# board.net
KiCad netlist of a schematic drawn in EAGLE
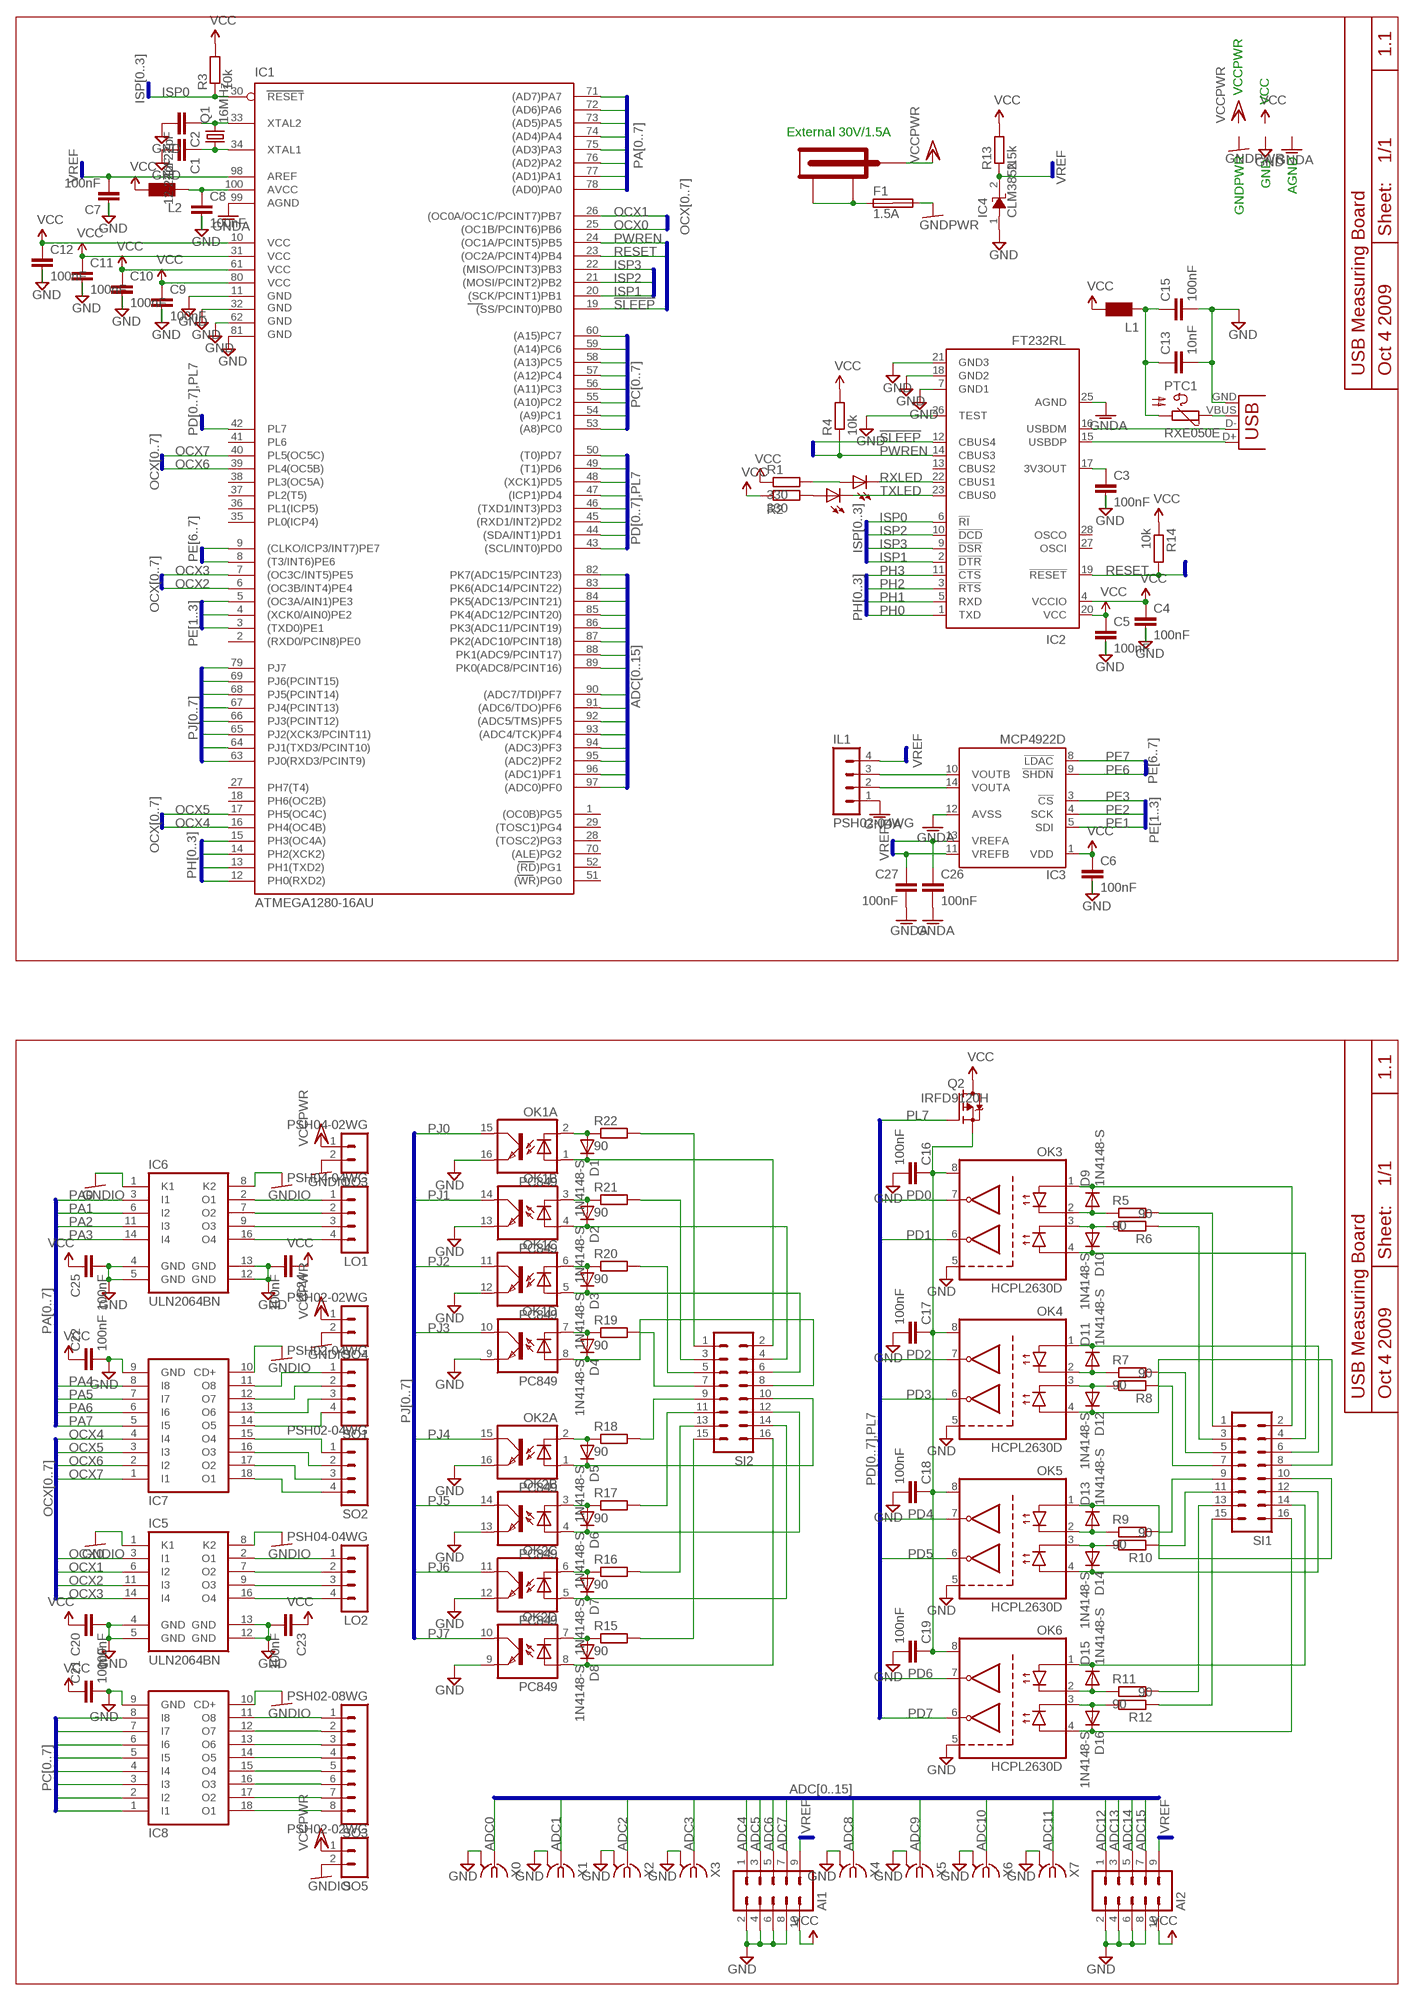
[diagram p0: schematic, sheet 1]

(export (version "E")
  (design (tool "Eeschema 10.0.6"))
  (components
    (comp (ref "AI1")
      (value "ML10")
      (footprint "eagle-import:ML10")
      (libsource (lib "eagle-import") (part "ML10"))
    )
    (comp (ref "AI2")
      (value "ML10")
      (footprint "eagle-import:ML10")
      (libsource (lib "eagle-import") (part "ML10"))
    )
    (comp (ref "C1")
      (value "12-22pF")
      (footprint "eagle-import:C0805K")
      (libsource (lib "eagle-import") (part "C-EUC0805K"))
    )
    (comp (ref "C2")
      (value "12-22pF")
      (footprint "eagle-import:C0805K")
      (libsource (lib "eagle-import") (part "C-EUC0805K"))
    )
    (comp (ref "C3")
      (value "100nF")
      (footprint "eagle-import:C0805K")
      (libsource (lib "eagle-import") (part "C-EUC0805K"))
    )
    (comp (ref "C4")
      (value "100nF")
      (footprint "eagle-import:C0805K")
      (libsource (lib "eagle-import") (part "C-EUC0805K"))
    )
    (comp (ref "C5")
      (value "100nF")
      (footprint "eagle-import:C0805K")
      (libsource (lib "eagle-import") (part "C-EUC0805K"))
    )
    (comp (ref "C6")
      (value "100nF")
      (footprint "eagle-import:C0805K")
      (libsource (lib "eagle-import") (part "C-EUC0805K"))
    )
    (comp (ref "C7")
      (value "100nF")
      (footprint "eagle-import:C0805K")
      (libsource (lib "eagle-import") (part "C-EUC0805K"))
    )
    (comp (ref "C8")
      (value "100nF")
      (footprint "eagle-import:C0805K")
      (libsource (lib "eagle-import") (part "C-EUC0805K"))
    )
    (comp (ref "C9")
      (value "100nF")
      (footprint "eagle-import:C0805K")
      (libsource (lib "eagle-import") (part "C-EUC0805K"))
    )
    (comp (ref "C10")
      (value "100nF")
      (footprint "eagle-import:C0805K")
      (libsource (lib "eagle-import") (part "C-EUC0805K"))
    )
    (comp (ref "C11")
      (value "100nF")
      (footprint "eagle-import:C0805K")
      (libsource (lib "eagle-import") (part "C-EUC0805K"))
    )
    (comp (ref "C12")
      (value "100nF")
      (footprint "eagle-import:C0805K")
      (libsource (lib "eagle-import") (part "C-EUC0805K"))
    )
    (comp (ref "C13")
      (value "10nF")
      (footprint "eagle-import:C0805K")
      (libsource (lib "eagle-import") (part "C-EUC0805K"))
    )
    (comp (ref "C15")
      (value "100nF")
      (footprint "eagle-import:C0805K")
      (libsource (lib "eagle-import") (part "C-EUC0805K"))
    )
    (comp (ref "C16")
      (value "100nF")
      (footprint "eagle-import:C0805K")
      (libsource (lib "eagle-import") (part "C-EUC0805K"))
    )
    (comp (ref "C17")
      (value "100nF")
      (footprint "eagle-import:C0805K")
      (libsource (lib "eagle-import") (part "C-EUC0805K"))
    )
    (comp (ref "C18")
      (value "100nF")
      (footprint "eagle-import:C0805K")
      (libsource (lib "eagle-import") (part "C-EUC0805K"))
    )
    (comp (ref "C19")
      (value "100nF")
      (footprint "eagle-import:C0805K")
      (libsource (lib "eagle-import") (part "C-EUC0805K"))
    )
    (comp (ref "C20")
      (value "100nF")
      (footprint "eagle-import:C0805K")
      (libsource (lib "eagle-import") (part "C-EUC0805K"))
    )
    (comp (ref "C21")
      (value "100nF")
      (footprint "eagle-import:C0805K")
      (libsource (lib "eagle-import") (part "C-EUC0805K"))
    )
    (comp (ref "C22")
      (value "100nF")
      (footprint "eagle-import:C0805K")
      (libsource (lib "eagle-import") (part "C-EUC0805K"))
    )
    (comp (ref "C23")
      (value "100nF")
      (footprint "eagle-import:C0805K")
      (libsource (lib "eagle-import") (part "C-EUC0805K"))
    )
    (comp (ref "C24")
      (value "100nF")
      (footprint "eagle-import:C0805K")
      (libsource (lib "eagle-import") (part "C-EUC0805K"))
    )
    (comp (ref "C25")
      (value "100nF")
      (footprint "eagle-import:C0805K")
      (libsource (lib "eagle-import") (part "C-EUC0805K"))
    )
    (comp (ref "C26")
      (value "100nF")
      (footprint "eagle-import:C0805K")
      (libsource (lib "eagle-import") (part "C-EUC0805K"))
    )
    (comp (ref "C27")
      (value "100nF")
      (footprint "eagle-import:C0805K")
      (libsource (lib "eagle-import") (part "C-EUC0805K"))
    )
    (comp (ref "CON1")
      (value "PWR-PCB")
      (footprint "eagle-import:PWR")
      (libsource (lib "eagle-import") (part "PWR-PCB"))
    )
    (comp (ref "D1")
      (value "1N4148-S")
      (footprint "eagle-import:D0805")
      (libsource (lib "eagle-import") (part "1N4148-S"))
    )
    (comp (ref "D2")
      (value "1N4148-S")
      (footprint "eagle-import:D0805")
      (libsource (lib "eagle-import") (part "1N4148-S"))
    )
    (comp (ref "D3")
      (value "1N4148-S")
      (footprint "eagle-import:D0805")
      (libsource (lib "eagle-import") (part "1N4148-S"))
    )
    (comp (ref "D4")
      (value "1N4148-S")
      (footprint "eagle-import:D0805")
      (libsource (lib "eagle-import") (part "1N4148-S"))
    )
    (comp (ref "D5")
      (value "1N4148-S")
      (footprint "eagle-import:D0805")
      (libsource (lib "eagle-import") (part "1N4148-S"))
    )
    (comp (ref "D6")
      (value "1N4148-S")
      (footprint "eagle-import:D0805")
      (libsource (lib "eagle-import") (part "1N4148-S"))
    )
    (comp (ref "D7")
      (value "1N4148-S")
      (footprint "eagle-import:D0805")
      (libsource (lib "eagle-import") (part "1N4148-S"))
    )
    (comp (ref "D8")
      (value "1N4148-S")
      (footprint "eagle-import:D0805")
      (libsource (lib "eagle-import") (part "1N4148-S"))
    )
    (comp (ref "D9")
      (value "1N4148-S")
      (footprint "eagle-import:D0805")
      (libsource (lib "eagle-import") (part "1N4148-S"))
    )
    (comp (ref "D10")
      (value "1N4148-S")
      (footprint "eagle-import:D0805")
      (libsource (lib "eagle-import") (part "1N4148-S"))
    )
    (comp (ref "D11")
      (value "1N4148-S")
      (footprint "eagle-import:D0805")
      (libsource (lib "eagle-import") (part "1N4148-S"))
    )
    (comp (ref "D12")
      (value "1N4148-S")
      (footprint "eagle-import:D0805")
      (libsource (lib "eagle-import") (part "1N4148-S"))
    )
    (comp (ref "D13")
      (value "1N4148-S")
      (footprint "eagle-import:D0805")
      (libsource (lib "eagle-import") (part "1N4148-S"))
    )
    (comp (ref "D14")
      (value "1N4148-S")
      (footprint "eagle-import:D0805")
      (libsource (lib "eagle-import") (part "1N4148-S"))
    )
    (comp (ref "D15")
      (value "1N4148-S")
      (footprint "eagle-import:D0805")
      (libsource (lib "eagle-import") (part "1N4148-S"))
    )
    (comp (ref "D16")
      (value "1N4148-S")
      (footprint "eagle-import:D0805")
      (libsource (lib "eagle-import") (part "1N4148-S"))
    )
    (comp (ref "F1")
      (value "1.5A")
      (footprint "eagle-import:FUSE-TH")
      (libsource (lib "eagle-import") (part "FUSE-TH"))
    )
    (comp (ref "IC1")
      (value "ATMEGA1280-16AU")
      (footprint "eagle-import:TQFP100")
      (libsource (lib "eagle-import") (part "ATMEGAAU640-16"))
    )
    (comp (ref "IC2")
      (value "FT232RL")
      (footprint "eagle-import:SSOP-28")
      (libsource (lib "eagle-import") (part "FT232RL"))
    )
    (comp (ref "IC3")
      (value "MCP4922D")
      (footprint "eagle-import:DIL-14")
      (libsource (lib "eagle-import") (part "MCP4922D"))
    )
    (comp (ref "IC4")
      (value "CLM385N")
      (footprint "eagle-import:TO-92")
      (libsource (lib "eagle-import") (part "CLM385N"))
    )
    (comp (ref "IC5")
      (value "ULN2064BN")
      (footprint "eagle-import:DIL16")
      (libsource (lib "eagle-import") (part "ULN2064BN"))
    )
    (comp (ref "IC6")
      (value "ULN2064BN")
      (footprint "eagle-import:DIL16")
      (libsource (lib "eagle-import") (part "ULN2064BN"))
    )
    (comp (ref "IC7")
      (value "ULN2803A")
      (footprint "eagle-import:DIL18")
      (libsource (lib "eagle-import") (part "ULN2803A"))
    )
    (comp (ref "IC8")
      (value "ULN2803A")
      (footprint "eagle-import:DIL18")
      (libsource (lib "eagle-import") (part "ULN2803A"))
    )
    (comp (ref "IL1")
      (value "PSH02-04WG")
      (footprint "eagle-import:PSH02-04WG")
      (libsource (lib "eagle-import") (part "PSH02-04WG"))
    )
    (comp (ref "L1")
      (value "FB-TH")
      (footprint "eagle-import:FB-2")
      (libsource (lib "eagle-import") (part "FB-TH"))
    )
    (comp (ref "L2")
      (value "FB-TH")
      (footprint "eagle-import:FB-2")
      (libsource (lib "eagle-import") (part "FB-TH"))
    )
    (comp (ref "LO1")
      (value "PSH04-04WG")
      (footprint "eagle-import:PSH04-04WG")
      (libsource (lib "eagle-import") (part "PSH04-04WG"))
    )
    (comp (ref "LO2")
      (value "PSH04-04WG")
      (footprint "eagle-import:PSH04-04WG")
      (libsource (lib "eagle-import") (part "PSH04-04WG"))
    )
    (comp (ref "LO3")
      (value "PSH04-02WG")
      (footprint "eagle-import:PSH04-02WG")
      (libsource (lib "eagle-import") (part "PSH04-02WG"))
    )
    (comp (ref "OK1")
      (value "PC849")
      (footprint "eagle-import:DIL-16")
      (libsource (lib "eagle-import") (part "PC849"))
    )
    (comp (ref "OK2")
      (value "PC849")
      (footprint "eagle-import:DIL-16")
      (libsource (lib "eagle-import") (part "PC849"))
    )
    (comp (ref "OK3")
      (value "HCPL2630D")
      (footprint "eagle-import:DIL-8")
      (libsource (lib "eagle-import") (part "HCPL2630D"))
    )
    (comp (ref "OK4")
      (value "HCPL2630D")
      (footprint "eagle-import:DIL-8")
      (libsource (lib "eagle-import") (part "HCPL2630D"))
    )
    (comp (ref "OK5")
      (value "HCPL2630D")
      (footprint "eagle-import:DIL-8")
      (libsource (lib "eagle-import") (part "HCPL2630D"))
    )
    (comp (ref "OK6")
      (value "HCPL2630D")
      (footprint "eagle-import:DIL-8")
      (libsource (lib "eagle-import") (part "HCPL2630D"))
    )
    (comp (ref "PTC1")
      (value "RXE050E")
      (footprint "eagle-import:RXE")
      (libsource (lib "eagle-import") (part "PTC-RXED"))
    )
    (comp (ref "Q1")
      (value "16MHz")
      (footprint "eagle-import:HC49_S")
      (libsource (lib "eagle-import") (part "CRYSTALHC49S"))
    )
    (comp (ref "Q2")
      (value "IRFD9120H")
      (footprint "eagle-import:HEXDIL-4")
      (libsource (lib "eagle-import") (part "IRFD9120H"))
    )
    (comp (ref "R1")
      (value "330")
      (footprint "eagle-import:M0805")
      (libsource (lib "eagle-import") (part "R-EU_M0805"))
    )
    (comp (ref "R2")
      (value "330")
      (footprint "eagle-import:M0805")
      (libsource (lib "eagle-import") (part "R-EU_M0805"))
    )
    (comp (ref "R3")
      (value "10k")
      (footprint "eagle-import:M0805")
      (libsource (lib "eagle-import") (part "R-EU_M0805"))
    )
    (comp (ref "R4")
      (value "10k")
      (footprint "eagle-import:M0805")
      (libsource (lib "eagle-import") (part "R-EU_M0805"))
    )
    (comp (ref "R5")
      (value "90")
      (footprint "eagle-import:M0805")
      (libsource (lib "eagle-import") (part "R-EU_M0805"))
    )
    (comp (ref "R6")
      (value "90")
      (footprint "eagle-import:M0805")
      (libsource (lib "eagle-import") (part "R-EU_M0805"))
    )
    (comp (ref "R7")
      (value "90")
      (footprint "eagle-import:M0805")
      (libsource (lib "eagle-import") (part "R-EU_M0805"))
    )
    (comp (ref "R8")
      (value "90")
      (footprint "eagle-import:M0805")
      (libsource (lib "eagle-import") (part "R-EU_M0805"))
    )
    (comp (ref "R9")
      (value "90")
      (footprint "eagle-import:M0805")
      (libsource (lib "eagle-import") (part "R-EU_M0805"))
    )
    (comp (ref "R10")
      (value "90")
      (footprint "eagle-import:M0805")
      (libsource (lib "eagle-import") (part "R-EU_M0805"))
    )
    (comp (ref "R11")
      (value "90")
      (footprint "eagle-import:M0805")
      (libsource (lib "eagle-import") (part "R-EU_M0805"))
    )
    (comp (ref "R12")
      (value "90")
      (footprint "eagle-import:M0805")
      (libsource (lib "eagle-import") (part "R-EU_M0805"))
    )
    (comp (ref "R13")
      (value "2.5k")
      (footprint "eagle-import:M0805")
      (libsource (lib "eagle-import") (part "R-EU_M0805"))
    )
    (comp (ref "R14")
      (value "10k")
      (footprint "eagle-import:M0805")
      (libsource (lib "eagle-import") (part "R-EU_M0805"))
    )
    (comp (ref "R15")
      (value "90")
      (footprint "eagle-import:M0805")
      (libsource (lib "eagle-import") (part "R-EU_M0805"))
    )
    (comp (ref "R16")
      (value "90")
      (footprint "eagle-import:M0805")
      (libsource (lib "eagle-import") (part "R-EU_M0805"))
    )
    (comp (ref "R17")
      (value "90")
      (footprint "eagle-import:M0805")
      (libsource (lib "eagle-import") (part "R-EU_M0805"))
    )
    (comp (ref "R18")
      (value "90")
      (footprint "eagle-import:M0805")
      (libsource (lib "eagle-import") (part "R-EU_M0805"))
    )
    (comp (ref "R19")
      (value "90")
      (footprint "eagle-import:M0805")
      (libsource (lib "eagle-import") (part "R-EU_M0805"))
    )
    (comp (ref "R20")
      (value "90")
      (footprint "eagle-import:M0805")
      (libsource (lib "eagle-import") (part "R-EU_M0805"))
    )
    (comp (ref "R21")
      (value "90")
      (footprint "eagle-import:M0805")
      (libsource (lib "eagle-import") (part "R-EU_M0805"))
    )
    (comp (ref "R22")
      (value "90")
      (footprint "eagle-import:M0805")
      (libsource (lib "eagle-import") (part "R-EU_M0805"))
    )
    (comp (ref "RXLED")
      (value "LED3MM")
      (footprint "eagle-import:LED3MM")
      (libsource (lib "eagle-import") (part "LED3MM"))
    )
    (comp (ref "SI1")
      (value "ML16")
      (footprint "eagle-import:ML16")
      (libsource (lib "eagle-import") (part "ML16"))
    )
    (comp (ref "SI2")
      (value "ML16")
      (footprint "eagle-import:ML16")
      (libsource (lib "eagle-import") (part "ML16"))
    )
    (comp (ref "SO1")
      (value "PSH02-04WG")
      (footprint "eagle-import:PSH02-04WG")
      (libsource (lib "eagle-import") (part "PSH02-04WG"))
    )
    (comp (ref "SO2")
      (value "PSH02-04WG")
      (footprint "eagle-import:PSH02-04WG")
      (libsource (lib "eagle-import") (part "PSH02-04WG"))
    )
    (comp (ref "SO3")
      (value "PSH02-08WG")
      (footprint "eagle-import:PSH02-08WG")
      (libsource (lib "eagle-import") (part "PSH02-08WG"))
    )
    (comp (ref "SO4")
      (value "PSH02-02WG")
      (footprint "eagle-import:PSH02-02WG")
      (libsource (lib "eagle-import") (part "PSH02-02WG"))
    )
    (comp (ref "SO5")
      (value "PSH02-02WG")
      (footprint "eagle-import:PSH02-02WG")
      (libsource (lib "eagle-import") (part "PSH02-02WG"))
    )
    (comp (ref "TXLED")
      (value "LED3MM")
      (footprint "eagle-import:LED3MM")
      (libsource (lib "eagle-import") (part "LED3MM"))
    )
    (comp (ref "USB1")
      (value "USB-PTH")
      (footprint "eagle-import:USB-B-PTH")
      (libsource (lib "eagle-import") (part "USB-PTH"))
    )
    (comp (ref "X0")
      (value "SMB-H")
      (footprint "eagle-import:SMB-H")
      (libsource (lib "eagle-import") (part "SMB-H"))
    )
    (comp (ref "X1")
      (value "SMB-H")
      (footprint "eagle-import:SMB-H")
      (libsource (lib "eagle-import") (part "SMB-H"))
    )
    (comp (ref "X2")
      (value "SMB-H")
      (footprint "eagle-import:SMB-H")
      (libsource (lib "eagle-import") (part "SMB-H"))
    )
    (comp (ref "X3")
      (value "SMB-H")
      (footprint "eagle-import:SMB-H")
      (libsource (lib "eagle-import") (part "SMB-H"))
    )
    (comp (ref "X4")
      (value "SMB-H")
      (footprint "eagle-import:SMB-H")
      (libsource (lib "eagle-import") (part "SMB-H"))
    )
    (comp (ref "X5")
      (value "SMB-H")
      (footprint "eagle-import:SMB-H")
      (libsource (lib "eagle-import") (part "SMB-H"))
    )
    (comp (ref "X6")
      (value "SMB-H")
      (footprint "eagle-import:SMB-H")
      (libsource (lib "eagle-import") (part "SMB-H"))
    )
    (comp (ref "X7")
      (value "SMB-H")
      (footprint "eagle-import:SMB-H")
      (libsource (lib "eagle-import") (part "SMB-H"))
    )
  )
  (nets
    (net (code "12") (name "ADC0") (class "Default")
      (node (ref "IC1") (pin "97") (pinfunction "(ADC0)PF0_97") (pintype "bidirectional"))
      (node (ref "X0") (pin "1") (pinfunction "1_1") (pintype "passive"))
    )
    (net (code "13") (name "ADC1") (class "Default")
      (node (ref "IC1") (pin "96") (pinfunction "(ADC1)PF1_96") (pintype "bidirectional"))
      (node (ref "X1") (pin "1") (pinfunction "1_1") (pintype "passive"))
    )
    (net (code "14") (name "ADC2") (class "Default")
      (node (ref "IC1") (pin "95") (pinfunction "(ADC2)PF2_95") (pintype "bidirectional"))
      (node (ref "X2") (pin "1") (pinfunction "1_1") (pintype "passive"))
    )
    (net (code "15") (name "ADC3") (class "Default")
      (node (ref "IC1") (pin "94") (pinfunction "(ADC3)PF3_94") (pintype "bidirectional"))
      (node (ref "X3") (pin "1") (pinfunction "1_1") (pintype "passive"))
    )
    (net (code "16") (name "ADC4") (class "Default")
      (node (ref "AI1") (pin "1") (pinfunction "1_1") (pintype "passive"))
      (node (ref "IC1") (pin "93") (pinfunction "(ADC4/TCK)PF4_93") (pintype "bidirectional"))
    )
    (net (code "17") (name "ADC5") (class "Default")
      (node (ref "AI1") (pin "3") (pinfunction "3_3") (pintype "passive"))
      (node (ref "IC1") (pin "92") (pinfunction "(ADC5/TMS)PF5_92") (pintype "bidirectional"))
    )
    (net (code "18") (name "ADC6") (class "Default")
      (node (ref "AI1") (pin "5") (pinfunction "5_5") (pintype "passive"))
      (node (ref "IC1") (pin "91") (pinfunction "(ADC6/TDO)PF6_91") (pintype "bidirectional"))
    )
    (net (code "19") (name "ADC7") (class "Default")
      (node (ref "AI1") (pin "7") (pinfunction "7_7") (pintype "passive"))
      (node (ref "IC1") (pin "90") (pinfunction "(ADC7/TDI)PF7_90") (pintype "bidirectional"))
    )
    (net (code "20") (name "ADC8") (class "Default")
      (node (ref "IC1") (pin "89") (pinfunction "PK0(ADC8/PCINT16)_89") (pintype "bidirectional"))
      (node (ref "X4") (pin "1") (pinfunction "1_1") (pintype "passive"))
    )
    (net (code "21") (name "ADC9") (class "Default")
      (node (ref "IC1") (pin "88") (pinfunction "PK1(ADC9/PCINT17)_88") (pintype "bidirectional"))
      (node (ref "X5") (pin "1") (pinfunction "1_1") (pintype "passive"))
    )
    (net (code "22") (name "ADC10") (class "Default")
      (node (ref "IC1") (pin "87") (pinfunction "PK2(ADC10/PCINT18)_87") (pintype "bidirectional"))
      (node (ref "X6") (pin "1") (pinfunction "1_1") (pintype "passive"))
    )
    (net (code "23") (name "ADC11") (class "Default")
      (node (ref "IC1") (pin "86") (pinfunction "PK3(ADC11/PCINT19)_86") (pintype "bidirectional"))
      (node (ref "X7") (pin "1") (pinfunction "1_1") (pintype "passive"))
    )
    (net (code "24") (name "ADC12") (class "Default")
      (node (ref "AI2") (pin "1") (pinfunction "1_1") (pintype "passive"))
      (node (ref "IC1") (pin "85") (pinfunction "PK4(ADC12/PCINT20)_85") (pintype "bidirectional"))
    )
    (net (code "25") (name "ADC13") (class "Default")
      (node (ref "AI2") (pin "3") (pinfunction "3_3") (pintype "passive"))
      (node (ref "IC1") (pin "84") (pinfunction "PK5(ADC13/PCINT21)_84") (pintype "bidirectional"))
    )
    (net (code "26") (name "ADC14") (class "Default")
      (node (ref "AI2") (pin "5") (pinfunction "5_5") (pintype "passive"))
      (node (ref "IC1") (pin "83") (pinfunction "PK6(ADC14/PCINT22)_83") (pintype "bidirectional"))
    )
    (net (code "27") (name "ADC15") (class "Default")
      (node (ref "AI2") (pin "7") (pinfunction "7_7") (pintype "passive"))
      (node (ref "IC1") (pin "82") (pinfunction "PK7(ADC15/PCINT23)_82") (pintype "bidirectional"))
    )
    (net (code "28") (name "GND") (class "Default")
      (node (ref "AI1") (pin "2") (pinfunction "2_2") (pintype "passive"))
      (node (ref "AI1") (pin "4") (pinfunction "4_4") (pintype "passive"))
      (node (ref "AI1") (pin "6") (pinfunction "6_6") (pintype "passive"))
      (node (ref "AI1") (pin "8") (pinfunction "8_8") (pintype "passive"))
      (node (ref "AI2") (pin "2") (pinfunction "2_2") (pintype "passive"))
      (node (ref "AI2") (pin "4") (pinfunction "4_4") (pintype "passive"))
      (node (ref "AI2") (pin "6") (pinfunction "6_6") (pintype "passive"))
      (node (ref "AI2") (pin "8") (pinfunction "8_8") (pintype "passive"))
      (node (ref "C1") (pin "2") (pinfunction "2_2") (pintype "passive"))
      (node (ref "C10") (pin "2") (pinfunction "2_2") (pintype "passive"))
      (node (ref "C11") (pin "2") (pinfunction "2_2") (pintype "passive"))
      (node (ref "C12") (pin "2") (pinfunction "2_2") (pintype "passive"))
      (node (ref "C13") (pin "2") (pinfunction "2_2") (pintype "passive"))
      (node (ref "C15") (pin "2") (pinfunction "2_2") (pintype "passive"))
      (node (ref "C16") (pin "2") (pinfunction "2_2") (pintype "passive"))
      (node (ref "C17") (pin "2") (pinfunction "2_2") (pintype "passive"))
      (node (ref "C18") (pin "2") (pinfunction "2_2") (pintype "passive"))
      (node (ref "C19") (pin "2") (pinfunction "2_2") (pintype "passive"))
      (node (ref "C2") (pin "2") (pinfunction "2_2") (pintype "passive"))
      (node (ref "C20") (pin "2") (pinfunction "2_2") (pintype "passive"))
      (node (ref "C21") (pin "2") (pinfunction "2_2") (pintype "passive"))
      (node (ref "C22") (pin "2") (pinfunction "2_2") (pintype "passive"))
      (node (ref "C23") (pin "2") (pinfunction "2_2") (pintype "passive"))
      (node (ref "C24") (pin "2") (pinfunction "2_2") (pintype "passive"))
      (node (ref "C25") (pin "2") (pinfunction "2_2") (pintype "passive"))
      (node (ref "C3") (pin "2") (pinfunction "2_2") (pintype "passive"))
      (node (ref "C4") (pin "2") (pinfunction "2_2") (pintype "passive"))
      (node (ref "C5") (pin "2") (pinfunction "2_2") (pintype "passive"))
      (node (ref "C6") (pin "2") (pinfunction "2_2") (pintype "passive"))
      (node (ref "C7") (pin "1") (pinfunction "1_1") (pintype "passive"))
      (node (ref "C8") (pin "2") (pinfunction "2_2") (pintype "passive"))
      (node (ref "C9") (pin "2") (pinfunction "2_2") (pintype "passive"))
      (node (ref "IC1") (pin "11") (pinfunction "GND_11") (pintype "power_in"))
      (node (ref "IC1") (pin "32") (pinfunction "GND1_32") (pintype "power_in"))
      (node (ref "IC1") (pin "62") (pinfunction "GND2_62") (pintype "power_in"))
      (node (ref "IC1") (pin "81") (pinfunction "GND3_81") (pintype "power_in"))
      (node (ref "IC2") (pin "18") (pinfunction "GND2_18") (pintype "input"))
      (node (ref "IC2") (pin "21") (pinfunction "GND3_21") (pintype "input"))
      (node (ref "IC2") (pin "26") (pinfunction "TEST_26") (pintype "input"))
      (node (ref "IC2") (pin "7") (pinfunction "GND1_7") (pintype "input"))
      (node (ref "IC4") (pin "1") (pinfunction "ANO_1") (pintype "input"))
      (node (ref "IC5") (pin "12") (pinfunction "GND_12") (pintype "power_in"))
      (node (ref "IC5") (pin "13") (pinfunction "GND_13") (pintype "power_in"))
      (node (ref "IC5") (pin "4") (pinfunction "GND_4") (pintype "power_in"))
      (node (ref "IC5") (pin "5") (pinfunction "GND_5") (pintype "power_in"))
      (node (ref "IC6") (pin "12") (pinfunction "GND_12") (pintype "power_in"))
      (node (ref "IC6") (pin "13") (pinfunction "GND_13") (pintype "power_in"))
      (node (ref "IC6") (pin "4") (pinfunction "GND_4") (pintype "power_in"))
      (node (ref "IC6") (pin "5") (pinfunction "GND_5") (pintype "power_in"))
      (node (ref "IC7") (pin "9") (pinfunction "GND_9") (pintype "power_in"))
      (node (ref "IC8") (pin "9") (pinfunction "GND_9") (pintype "power_in"))
      (node (ref "OK1") (pin "12") (pinfunction "EMI_12") (pintype "passive"))
      (node (ref "OK1") (pin "13") (pinfunction "EMI_13") (pintype "passive"))
      (node (ref "OK1") (pin "16") (pinfunction "EMI_16") (pintype "passive"))
      (node (ref "OK1") (pin "9") (pinfunction "EMI_9") (pintype "passive"))
      (node (ref "OK2") (pin "12") (pinfunction "EMI_12") (pintype "passive"))
      (node (ref "OK2") (pin "13") (pinfunction "EMI_13") (pintype "passive"))
      (node (ref "OK2") (pin "16") (pinfunction "EMI_16") (pintype "passive"))
      (node (ref "OK2") (pin "9") (pinfunction "EMI_9") (pintype "passive"))
      (node (ref "OK3") (pin "5") (pinfunction "GND_5") (pintype "power_in"))
      (node (ref "OK4") (pin "5") (pinfunction "GND_5") (pintype "power_in"))
      (node (ref "OK5") (pin "5") (pinfunction "GND_5") (pintype "power_in"))
      (node (ref "OK6") (pin "5") (pinfunction "GND_5") (pintype "power_in"))
      (node (ref "USB1") (pin "GND") (pinfunction "GND_GND") (pintype "bidirectional"))
      (node (ref "X0") (pin "2") (pinfunction "GND_2") (pintype "power_in"))
      (node (ref "X1") (pin "2") (pinfunction "GND_2") (pintype "power_in"))
      (node (ref "X2") (pin "2") (pinfunction "GND_2") (pintype "power_in"))
      (node (ref "X3") (pin "2") (pinfunction "GND_2") (pintype "power_in"))
      (node (ref "X4") (pin "2") (pinfunction "GND_2") (pintype "power_in"))
      (node (ref "X5") (pin "2") (pinfunction "GND_2") (pintype "power_in"))
      (node (ref "X6") (pin "2") (pinfunction "GND_2") (pintype "power_in"))
      (node (ref "X7") (pin "2") (pinfunction "GND_2") (pintype "power_in"))
    )
    (net (code "29") (name "GNDA") (class "Default")
      (node (ref "C26") (pin "2") (pinfunction "2_2") (pintype "passive"))
      (node (ref "C27") (pin "2") (pinfunction "2_2") (pintype "passive"))
      (node (ref "IC1") (pin "99") (pinfunction "AGND_99") (pintype "power_in"))
      (node (ref "IC2") (pin "25") (pinfunction "AGND_25") (pintype "input"))
      (node (ref "IC3") (pin "12") (pinfunction "AVSS_12") (pintype "power_in"))
      (node (ref "IL1") (pin "1") (pinfunction "1_1") (pintype "passive"))
    )
    (net (code "30") (name "GNDIO") (class "Default")
      (node (ref "F1") (pin "2A") (pinfunction "2A_2A") (pintype "passive"))
      (node (ref "IC5") (pin "1") (pinfunction "K1_1") (pintype "passive"))
      (node (ref "IC5") (pin "8") (pinfunction "K2_8") (pintype "passive"))
      (node (ref "IC6") (pin "1") (pinfunction "K1_1") (pintype "passive"))
      (node (ref "IC6") (pin "8") (pinfunction "K2_8") (pintype "passive"))
      (node (ref "IC7") (pin "10") (pinfunction "CD+_10") (pintype "passive"))
      (node (ref "IC8") (pin "10") (pinfunction "CD+_10") (pintype "passive"))
      (node (ref "LO3") (pin "2") (pinfunction "2_2") (pintype "passive"))
      (node (ref "SO4") (pin "2") (pinfunction "2_2") (pintype "passive"))
      (node (ref "SO5") (pin "2") (pinfunction "2_2") (pintype "passive"))
    )
    (net (code "31") (name "ISP0") (class "Default")
      (node (ref "IC1") (pin "30") (pinfunction "RESET_30") (pintype "input"))
      (node (ref "IC2") (pin "6") (pinfunction "~{RI}_6") (pintype "input"))
      (node (ref "R3") (pin "1") (pinfunction "1_1") (pintype "passive"))
    )
    (net (code "32") (name "ISP1") (class "Default")
      (node (ref "IC1") (pin "20") (pinfunction "(SCK/PCINT1)PB1_20") (pintype "bidirectional"))
      (node (ref "IC2") (pin "2") (pinfunction "~{DTR}_2") (pintype "input"))
    )
    (net (code "33") (name "ISP2") (class "Default")
      (node (ref "IC1") (pin "21") (pinfunction "(MOSI/PCINT2)PB2_21") (pintype "bidirectional"))
      (node (ref "IC2") (pin "10") (pinfunction "~{DCD}_10") (pintype "input"))
    )
    (net (code "34") (name "ISP3") (class "Default")
      (node (ref "IC1") (pin "22") (pinfunction "(MISO/PCINT3)PB3_22") (pintype "bidirectional"))
      (node (ref "IC2") (pin "9") (pinfunction "~{DSR}_9") (pintype "input"))
    )
    (net (code "35") (name "Net-(C13-Pad1)") (class "Default")
      (node (ref "C13") (pin "1") (pinfunction "1_1") (pintype "passive"))
      (node (ref "C15") (pin "1") (pinfunction "1_1") (pintype "passive"))
      (node (ref "L1") (pin "1") (pinfunction "1_1") (pintype "passive"))
      (node (ref "PTC1") (pin "2") (pinfunction "2_2") (pintype "passive"))
    )
    (net (code "36") (name "Net-(CON1-GND-PadGND1)") (class "Default")
      (node (ref "CON1") (pin "GND1") (pinfunction "GND_GND1") (pintype "power_in"))
      (node (ref "CON1") (pin "GND2") (pinfunction "GND_GND2") (pintype "power_in"))
      (node (ref "F1") (pin "1A") (pinfunction "1A_1A") (pintype "passive"))
    )
    (net (code "37") (name "Net-(D1-A)") (class "Default")
      (node (ref "D1") (pin "ANODE") (pinfunction "A_ANODE") (pintype "passive"))
      (node (ref "OK1") (pin "2") (pinfunction "C_2") (pintype "passive"))
      (node (ref "R22") (pin "1") (pinfunction "1_1") (pintype "passive"))
    )
    (net (code "38") (name "Net-(D1-C)") (class "Default")
      (node (ref "D1") (pin "CATHODE") (pinfunction "C_CATHODE") (pintype "passive"))
      (node (ref "OK1") (pin "1") (pinfunction "A_1") (pintype "passive"))
      (node (ref "SI2") (pin "2") (pinfunction "2_2") (pintype "passive"))
    )
    (net (code "39") (name "Net-(D2-A)") (class "Default")
      (node (ref "D2") (pin "ANODE") (pinfunction "A_ANODE") (pintype "passive"))
      (node (ref "OK1") (pin "3") (pinfunction "C_3") (pintype "passive"))
      (node (ref "R21") (pin "1") (pinfunction "1_1") (pintype "passive"))
    )
    (net (code "40") (name "Net-(D2-C)") (class "Default")
      (node (ref "D2") (pin "CATHODE") (pinfunction "C_CATHODE") (pintype "passive"))
      (node (ref "OK1") (pin "4") (pinfunction "A_4") (pintype "passive"))
      (node (ref "SI2") (pin "4") (pinfunction "4_4") (pintype "passive"))
    )
    (net (code "41") (name "Net-(D3-A)") (class "Default")
      (node (ref "D3") (pin "ANODE") (pinfunction "A_ANODE") (pintype "passive"))
      (node (ref "OK1") (pin "6") (pinfunction "C_6") (pintype "passive"))
      (node (ref "R20") (pin "1") (pinfunction "1_1") (pintype "passive"))
    )
    (net (code "42") (name "Net-(D3-C)") (class "Default")
      (node (ref "D3") (pin "CATHODE") (pinfunction "C_CATHODE") (pintype "passive"))
      (node (ref "OK1") (pin "5") (pinfunction "A_5") (pintype "passive"))
      (node (ref "SI2") (pin "6") (pinfunction "6_6") (pintype "passive"))
    )
    (net (code "43") (name "Net-(D4-A)") (class "Default")
      (node (ref "D4") (pin "ANODE") (pinfunction "A_ANODE") (pintype "passive"))
      (node (ref "OK1") (pin "7") (pinfunction "C_7") (pintype "passive"))
      (node (ref "R19") (pin "1") (pinfunction "1_1") (pintype "passive"))
    )
    (net (code "44") (name "Net-(D4-C)") (class "Default")
      (node (ref "D4") (pin "CATHODE") (pinfunction "C_CATHODE") (pintype "passive"))
      (node (ref "OK1") (pin "8") (pinfunction "A_8") (pintype "passive"))
      (node (ref "SI2") (pin "8") (pinfunction "8_8") (pintype "passive"))
    )
    (net (code "45") (name "Net-(D5-A)") (class "Default")
      (node (ref "D5") (pin "ANODE") (pinfunction "A_ANODE") (pintype "passive"))
      (node (ref "OK2") (pin "2") (pinfunction "C_2") (pintype "passive"))
      (node (ref "R18") (pin "1") (pinfunction "1_1") (pintype "passive"))
    )
    (net (code "46") (name "Net-(D5-C)") (class "Default")
      (node (ref "D5") (pin "CATHODE") (pinfunction "C_CATHODE") (pintype "passive"))
      (node (ref "OK2") (pin "1") (pinfunction "A_1") (pintype "passive"))
      (node (ref "SI2") (pin "10") (pinfunction "10_10") (pintype "passive"))
    )
    (net (code "47") (name "Net-(D6-A)") (class "Default")
      (node (ref "D6") (pin "ANODE") (pinfunction "A_ANODE") (pintype "passive"))
      (node (ref "OK2") (pin "3") (pinfunction "C_3") (pintype "passive"))
      (node (ref "R17") (pin "1") (pinfunction "1_1") (pintype "passive"))
    )
    (net (code "48") (name "Net-(D6-C)") (class "Default")
      (node (ref "D6") (pin "CATHODE") (pinfunction "C_CATHODE") (pintype "passive"))
      (node (ref "OK2") (pin "4") (pinfunction "A_4") (pintype "passive"))
      (node (ref "SI2") (pin "12") (pinfunction "12_12") (pintype "passive"))
    )
    (net (code "49") (name "Net-(D7-A)") (class "Default")
      (node (ref "D7") (pin "ANODE") (pinfunction "A_ANODE") (pintype "passive"))
      (node (ref "OK2") (pin "6") (pinfunction "C_6") (pintype "passive"))
      (node (ref "R16") (pin "1") (pinfunction "1_1") (pintype "passive"))
    )
    (net (code "50") (name "Net-(D7-C)") (class "Default")
      (node (ref "D7") (pin "CATHODE") (pinfunction "C_CATHODE") (pintype "passive"))
      (node (ref "OK2") (pin "5") (pinfunction "A_5") (pintype "passive"))
      (node (ref "SI2") (pin "14") (pinfunction "14_14") (pintype "passive"))
    )
    (net (code "51") (name "Net-(D8-A)") (class "Default")
      (node (ref "D8") (pin "ANODE") (pinfunction "A_ANODE") (pintype "passive"))
      (node (ref "OK2") (pin "7") (pinfunction "C_7") (pintype "passive"))
      (node (ref "R15") (pin "1") (pinfunction "1_1") (pintype "passive"))
    )
    (net (code "52") (name "Net-(D8-C)") (class "Default")
      (node (ref "D8") (pin "CATHODE") (pinfunction "C_CATHODE") (pintype "passive"))
      (node (ref "OK2") (pin "8") (pinfunction "A_8") (pintype "passive"))
      (node (ref "SI2") (pin "16") (pinfunction "16_16") (pintype "passive"))
    )
    (net (code "53") (name "Net-(D9-A)") (class "Default")
      (node (ref "D9") (pin "ANODE") (pinfunction "A_ANODE") (pintype "passive"))
      (node (ref "OK3") (pin "2") (pinfunction "KATHODE1_2") (pintype "input"))
      (node (ref "R5") (pin "1") (pinfunction "1_1") (pintype "passive"))
    )
    (net (code "54") (name "Net-(D9-C)") (class "Default")
      (node (ref "D9") (pin "CATHODE") (pinfunction "C_CATHODE") (pintype "passive"))
      (node (ref "OK3") (pin "1") (pinfunction "ANODE1_1") (pintype "input"))
      (node (ref "SI1") (pin "2") (pinfunction "2_2") (pintype "passive"))
    )
    (net (code "55") (name "Net-(D10-A)") (class "Default")
      (node (ref "D10") (pin "ANODE") (pinfunction "A_ANODE") (pintype "passive"))
      (node (ref "OK3") (pin "3") (pinfunction "KATHODE2_3") (pintype "input"))
      (node (ref "R6") (pin "2") (pinfunction "2_2") (pintype "passive"))
    )
    (net (code "56") (name "Net-(D10-C)") (class "Default")
      (node (ref "D10") (pin "CATHODE") (pinfunction "C_CATHODE") (pintype "passive"))
      (node (ref "OK3") (pin "4") (pinfunction "ANODE2_4") (pintype "input"))
      (node (ref "SI1") (pin "4") (pinfunction "4_4") (pintype "passive"))
    )
    (net (code "57") (name "Net-(D11-A)") (class "Default")
      (node (ref "D11") (pin "ANODE") (pinfunction "A_ANODE") (pintype "passive"))
      (node (ref "OK4") (pin "2") (pinfunction "KATHODE1_2") (pintype "input"))
      (node (ref "R7") (pin "1") (pinfunction "1_1") (pintype "passive"))
    )
    (net (code "58") (name "Net-(D11-C)") (class "Default")
      (node (ref "D11") (pin "CATHODE") (pinfunction "C_CATHODE") (pintype "passive"))
      (node (ref "OK4") (pin "1") (pinfunction "ANODE1_1") (pintype "input"))
      (node (ref "SI1") (pin "6") (pinfunction "6_6") (pintype "passive"))
    )
    (net (code "59") (name "Net-(D12-A)") (class "Default")
      (node (ref "D12") (pin "ANODE") (pinfunction "A_ANODE") (pintype "passive"))
      (node (ref "OK4") (pin "3") (pinfunction "KATHODE2_3") (pintype "input"))
      (node (ref "R8") (pin "2") (pinfunction "2_2") (pintype "passive"))
    )
    (net (code "60") (name "Net-(D12-C)") (class "Default")
      (node (ref "D12") (pin "CATHODE") (pinfunction "C_CATHODE") (pintype "passive"))
      (node (ref "OK4") (pin "4") (pinfunction "ANODE2_4") (pintype "input"))
      (node (ref "SI1") (pin "8") (pinfunction "8_8") (pintype "passive"))
    )
    (net (code "61") (name "Net-(D13-A)") (class "Default")
      (node (ref "D13") (pin "ANODE") (pinfunction "A_ANODE") (pintype "passive"))
      (node (ref "OK5") (pin "2") (pinfunction "KATHODE1_2") (pintype "input"))
      (node (ref "R9") (pin "1") (pinfunction "1_1") (pintype "passive"))
    )
    (net (code "62") (name "Net-(D13-C)") (class "Default")
      (node (ref "D13") (pin "CATHODE") (pinfunction "C_CATHODE") (pintype "passive"))
      (node (ref "OK5") (pin "1") (pinfunction "ANODE1_1") (pintype "input"))
      (node (ref "SI1") (pin "10") (pinfunction "10_10") (pintype "passive"))
    )
    (net (code "63") (name "Net-(D14-A)") (class "Default")
      (node (ref "D14") (pin "ANODE") (pinfunction "A_ANODE") (pintype "passive"))
      (node (ref "OK5") (pin "3") (pinfunction "KATHODE2_3") (pintype "input"))
      (node (ref "R10") (pin "2") (pinfunction "2_2") (pintype "passive"))
    )
    (net (code "64") (name "Net-(D14-C)") (class "Default")
      (node (ref "D14") (pin "CATHODE") (pinfunction "C_CATHODE") (pintype "passive"))
      (node (ref "OK5") (pin "4") (pinfunction "ANODE2_4") (pintype "input"))
      (node (ref "SI1") (pin "12") (pinfunction "12_12") (pintype "passive"))
    )
    (net (code "65") (name "Net-(D15-A)") (class "Default")
      (node (ref "D15") (pin "ANODE") (pinfunction "A_ANODE") (pintype "passive"))
      (node (ref "OK6") (pin "2") (pinfunction "KATHODE1_2") (pintype "input"))
      (node (ref "R11") (pin "1") (pinfunction "1_1") (pintype "passive"))
    )
    (net (code "66") (name "Net-(D15-C)") (class "Default")
      (node (ref "D15") (pin "CATHODE") (pinfunction "C_CATHODE") (pintype "passive"))
      (node (ref "OK6") (pin "1") (pinfunction "ANODE1_1") (pintype "input"))
      (node (ref "SI1") (pin "14") (pinfunction "14_14") (pintype "passive"))
    )
    (net (code "67") (name "Net-(D16-A)") (class "Default")
      (node (ref "D16") (pin "ANODE") (pinfunction "A_ANODE") (pintype "passive"))
      (node (ref "OK6") (pin "3") (pinfunction "KATHODE2_3") (pintype "input"))
      (node (ref "R12") (pin "2") (pinfunction "2_2") (pintype "passive"))
    )
    (net (code "68") (name "Net-(D16-C)") (class "Default")
      (node (ref "D16") (pin "CATHODE") (pinfunction "C_CATHODE") (pintype "passive"))
      (node (ref "OK6") (pin "4") (pinfunction "ANODE2_4") (pintype "input"))
      (node (ref "SI1") (pin "16") (pinfunction "16_16") (pintype "passive"))
    )
    (net (code "69") (name "Net-(IC1-AVCC)") (class "Default")
      (node (ref "C8") (pin "1") (pinfunction "1_1") (pintype "passive"))
      (node (ref "IC1") (pin "100") (pinfunction "AVCC_100") (pintype "power_in"))
      (node (ref "L2") (pin "1") (pinfunction "1_1") (pintype "passive"))
    )
    (net (code "70") (name "Net-(IC1-XTAL1)") (class "Default")
      (node (ref "C1") (pin "1") (pinfunction "1_1") (pintype "passive"))
      (node (ref "IC1") (pin "34") (pinfunction "XTAL1_34") (pintype "input"))
      (node (ref "Q1") (pin "1") (pinfunction "1_1") (pintype "passive"))
    )
    (net (code "71") (name "Net-(IC1-XTAL2)") (class "Default")
      (node (ref "C2") (pin "1") (pinfunction "1_1") (pintype "passive"))
      (node (ref "IC1") (pin "33") (pinfunction "XTAL2_33") (pintype "output"))
      (node (ref "Q1") (pin "2") (pinfunction "2_2") (pintype "passive"))
    )
    (net (code "72") (name "Net-(IC2-3V3OUT)") (class "Default")
      (node (ref "C3") (pin "1") (pinfunction "1_1") (pintype "passive"))
      (node (ref "IC2") (pin "17") (pinfunction "3V3OUT_17") (pintype "input"))
    )
    (net (code "73") (name "Net-(IC2-USBDM)") (class "Default")
      (node (ref "IC2") (pin "16") (pinfunction "USBDM_16") (pintype "input"))
      (node (ref "USB1") (pin "D-") (pinfunction "D-_D-") (pintype "bidirectional"))
    )
    (net (code "74") (name "Net-(IC2-USBDP)") (class "Default")
      (node (ref "IC2") (pin "15") (pinfunction "USBDP_15") (pintype "input"))
      (node (ref "USB1") (pin "D+") (pinfunction "D+_D+") (pintype "bidirectional"))
    )
    (net (code "75") (name "Net-(IC3-VOUTA)") (class "Default")
      (node (ref "IC3") (pin "14") (pinfunction "VOUTA_14") (pintype "passive"))
      (node (ref "IL1") (pin "2") (pinfunction "2_2") (pintype "passive"))
    )
    (net (code "76") (name "Net-(IC3-VOUTB)") (class "Default")
      (node (ref "IC3") (pin "10") (pinfunction "VOUTB_10") (pintype "passive"))
      (node (ref "IL1") (pin "3") (pinfunction "3_3") (pintype "passive"))
    )
    (net (code "77") (name "Net-(IC5-O1)") (class "Default")
      (node (ref "IC5") (pin "2") (pinfunction "O1_2") (pintype "open_collector"))
      (node (ref "LO2") (pin "1") (pinfunction "1_1") (pintype "passive"))
    )
    (net (code "78") (name "Net-(IC5-O2)") (class "Default")
      (node (ref "IC5") (pin "7") (pinfunction "O2_7") (pintype "open_collector"))
      (node (ref "LO2") (pin "2") (pinfunction "2_2") (pintype "passive"))
    )
    (net (code "79") (name "Net-(IC5-O3)") (class "Default")
      (node (ref "IC5") (pin "9") (pinfunction "O3_9") (pintype "open_collector"))
      (node (ref "LO2") (pin "3") (pinfunction "3_3") (pintype "passive"))
    )
    (net (code "80") (name "Net-(IC5-O4)") (class "Default")
      (node (ref "IC5") (pin "16") (pinfunction "O4_16") (pintype "open_collector"))
      (node (ref "LO2") (pin "4") (pinfunction "4_4") (pintype "passive"))
    )
    (net (code "81") (name "Net-(IC6-O1)") (class "Default")
      (node (ref "IC6") (pin "2") (pinfunction "O1_2") (pintype "open_collector"))
      (node (ref "LO1") (pin "1") (pinfunction "1_1") (pintype "passive"))
    )
    (net (code "82") (name "Net-(IC6-O2)") (class "Default")
      (node (ref "IC6") (pin "7") (pinfunction "O2_7") (pintype "open_collector"))
      (node (ref "LO1") (pin "2") (pinfunction "2_2") (pintype "passive"))
    )
    (net (code "83") (name "Net-(IC6-O3)") (class "Default")
      (node (ref "IC6") (pin "9") (pinfunction "O3_9") (pintype "open_collector"))
      (node (ref "LO1") (pin "3") (pinfunction "3_3") (pintype "passive"))
    )
    (net (code "84") (name "Net-(IC6-O4)") (class "Default")
      (node (ref "IC6") (pin "16") (pinfunction "O4_16") (pintype "open_collector"))
      (node (ref "LO1") (pin "4") (pinfunction "4_4") (pintype "passive"))
    )
    (net (code "85") (name "Net-(IC7-O1)") (class "Default")
      (node (ref "IC7") (pin "18") (pinfunction "O1_18") (pintype "open_collector"))
      (node (ref "SO2") (pin "4") (pinfunction "4_4") (pintype "passive"))
    )
    (net (code "86") (name "Net-(IC7-O2)") (class "Default")
      (node (ref "IC7") (pin "17") (pinfunction "O2_17") (pintype "open_collector"))
      (node (ref "SO2") (pin "3") (pinfunction "3_3") (pintype "passive"))
    )
    (net (code "87") (name "Net-(IC7-O3)") (class "Default")
      (node (ref "IC7") (pin "16") (pinfunction "O3_16") (pintype "open_collector"))
      (node (ref "SO2") (pin "2") (pinfunction "2_2") (pintype "passive"))
    )
    (net (code "88") (name "Net-(IC7-O4)") (class "Default")
      (node (ref "IC7") (pin "15") (pinfunction "O4_15") (pintype "open_collector"))
      (node (ref "SO2") (pin "1") (pinfunction "1_1") (pintype "passive"))
    )
    (net (code "89") (name "Net-(IC7-O5)") (class "Default")
      (node (ref "IC7") (pin "14") (pinfunction "O5_14") (pintype "open_collector"))
      (node (ref "SO1") (pin "4") (pinfunction "4_4") (pintype "passive"))
    )
    (net (code "90") (name "Net-(IC7-O6)") (class "Default")
      (node (ref "IC7") (pin "13") (pinfunction "O6_13") (pintype "open_collector"))
      (node (ref "SO1") (pin "3") (pinfunction "3_3") (pintype "passive"))
    )
    (net (code "91") (name "Net-(IC7-O7)") (class "Default")
      (node (ref "IC7") (pin "12") (pinfunction "O7_12") (pintype "open_collector"))
      (node (ref "SO1") (pin "2") (pinfunction "2_2") (pintype "passive"))
    )
    (net (code "92") (name "Net-(IC7-O8)") (class "Default")
      (node (ref "IC7") (pin "11") (pinfunction "O8_11") (pintype "open_collector"))
      (node (ref "SO1") (pin "1") (pinfunction "1_1") (pintype "passive"))
    )
    (net (code "93") (name "Net-(IC8-O1)") (class "Default")
      (node (ref "IC8") (pin "18") (pinfunction "O1_18") (pintype "open_collector"))
      (node (ref "SO3") (pin "8") (pinfunction "8_8") (pintype "passive"))
    )
    (net (code "94") (name "Net-(IC8-O2)") (class "Default")
      (node (ref "IC8") (pin "17") (pinfunction "O2_17") (pintype "open_collector"))
      (node (ref "SO3") (pin "7") (pinfunction "7_7") (pintype "passive"))
    )
    (net (code "95") (name "Net-(IC8-O3)") (class "Default")
      (node (ref "IC8") (pin "16") (pinfunction "O3_16") (pintype "open_collector"))
      (node (ref "SO3") (pin "6") (pinfunction "6_6") (pintype "passive"))
    )
    (net (code "96") (name "Net-(IC8-O4)") (class "Default")
      (node (ref "IC8") (pin "15") (pinfunction "O4_15") (pintype "open_collector"))
      (node (ref "SO3") (pin "5") (pinfunction "5_5") (pintype "passive"))
    )
    (net (code "97") (name "Net-(IC8-O5)") (class "Default")
      (node (ref "IC8") (pin "14") (pinfunction "O5_14") (pintype "open_collector"))
      (node (ref "SO3") (pin "4") (pinfunction "4_4") (pintype "passive"))
    )
    (net (code "98") (name "Net-(IC8-O6)") (class "Default")
      (node (ref "IC8") (pin "13") (pinfunction "O6_13") (pintype "open_collector"))
      (node (ref "SO3") (pin "3") (pinfunction "3_3") (pintype "passive"))
    )
    (net (code "99") (name "Net-(IC8-O7)") (class "Default")
      (node (ref "IC8") (pin "12") (pinfunction "O7_12") (pintype "open_collector"))
      (node (ref "SO3") (pin "2") (pinfunction "2_2") (pintype "passive"))
    )
    (net (code "100") (name "Net-(IC8-O8)") (class "Default")
      (node (ref "IC8") (pin "11") (pinfunction "O8_11") (pintype "open_collector"))
      (node (ref "SO3") (pin "1") (pinfunction "1_1") (pintype "passive"))
    )
    (net (code "101") (name "Net-(OK3-VCC)") (class "Default")
      (node (ref "C16") (pin "1") (pinfunction "1_1") (pintype "passive"))
      (node (ref "C17") (pin "1") (pinfunction "1_1") (pintype "passive"))
      (node (ref "C18") (pin "1") (pinfunction "1_1") (pintype "passive"))
      (node (ref "C19") (pin "1") (pinfunction "1_1") (pintype "passive"))
      (node (ref "OK3") (pin "8") (pinfunction "VCC_8") (pintype "power_in"))
      (node (ref "OK4") (pin "8") (pinfunction "VCC_8") (pintype "power_in"))
      (node (ref "OK5") (pin "8") (pinfunction "VCC_8") (pintype "power_in"))
      (node (ref "OK6") (pin "8") (pinfunction "VCC_8") (pintype "power_in"))
      (node (ref "Q2") (pin "2") (pinfunction "SOURCE_2") (pintype "passive"))
    )
    (net (code "102") (name "Net-(PTC1-Pad1)") (class "Default")
      (node (ref "PTC1") (pin "1") (pinfunction "1_1") (pintype "passive"))
      (node (ref "USB1") (pin "VBUS") (pinfunction "VBUS_VBUS") (pintype "bidirectional"))
    )
    (net (code "103") (name "Net-(R1-Pad2)") (class "Default")
      (node (ref "R1") (pin "2") (pinfunction "2_2") (pintype "passive"))
      (node (ref "RXLED") (pin "A") (pinfunction "A_A") (pintype "passive"))
    )
    (net (code "104") (name "Net-(R2-Pad2)") (class "Default")
      (node (ref "R2") (pin "2") (pinfunction "2_2") (pintype "passive"))
      (node (ref "TXLED") (pin "A") (pinfunction "A_A") (pintype "passive"))
    )
    (net (code "105") (name "Net-(R5-Pad2)") (class "Default")
      (node (ref "R5") (pin "2") (pinfunction "2_2") (pintype "passive"))
      (node (ref "SI1") (pin "1") (pinfunction "1_1") (pintype "passive"))
    )
    (net (code "106") (name "Net-(R6-Pad1)") (class "Default")
      (node (ref "R6") (pin "1") (pinfunction "1_1") (pintype "passive"))
      (node (ref "SI1") (pin "3") (pinfunction "3_3") (pintype "passive"))
    )
    (net (code "107") (name "Net-(R7-Pad2)") (class "Default")
      (node (ref "R7") (pin "2") (pinfunction "2_2") (pintype "passive"))
      (node (ref "SI1") (pin "5") (pinfunction "5_5") (pintype "passive"))
    )
    (net (code "108") (name "Net-(R8-Pad1)") (class "Default")
      (node (ref "R8") (pin "1") (pinfunction "1_1") (pintype "passive"))
      (node (ref "SI1") (pin "7") (pinfunction "7_7") (pintype "passive"))
    )
    (net (code "109") (name "Net-(R9-Pad2)") (class "Default")
      (node (ref "R9") (pin "2") (pinfunction "2_2") (pintype "passive"))
      (node (ref "SI1") (pin "9") (pinfunction "9_9") (pintype "passive"))
    )
    (net (code "110") (name "Net-(R10-Pad1)") (class "Default")
      (node (ref "R10") (pin "1") (pinfunction "1_1") (pintype "passive"))
      (node (ref "SI1") (pin "11") (pinfunction "11_11") (pintype "passive"))
    )
    (net (code "111") (name "Net-(R11-Pad2)") (class "Default")
      (node (ref "R11") (pin "2") (pinfunction "2_2") (pintype "passive"))
      (node (ref "SI1") (pin "13") (pinfunction "13_13") (pintype "passive"))
    )
    (net (code "112") (name "Net-(R12-Pad1)") (class "Default")
      (node (ref "R12") (pin "1") (pinfunction "1_1") (pintype "passive"))
      (node (ref "SI1") (pin "15") (pinfunction "15_15") (pintype "passive"))
    )
    (net (code "113") (name "Net-(R15-Pad2)") (class "Default")
      (node (ref "R15") (pin "2") (pinfunction "2_2") (pintype "passive"))
      (node (ref "SI2") (pin "15") (pinfunction "15_15") (pintype "passive"))
    )
    (net (code "114") (name "Net-(R16-Pad2)") (class "Default")
      (node (ref "R16") (pin "2") (pinfunction "2_2") (pintype "passive"))
      (node (ref "SI2") (pin "13") (pinfunction "13_13") (pintype "passive"))
    )
    (net (code "115") (name "Net-(R17-Pad2)") (class "Default")
      (node (ref "R17") (pin "2") (pinfunction "2_2") (pintype "passive"))
      (node (ref "SI2") (pin "11") (pinfunction "11_11") (pintype "passive"))
    )
    (net (code "116") (name "Net-(R18-Pad2)") (class "Default")
      (node (ref "R18") (pin "2") (pinfunction "2_2") (pintype "passive"))
      (node (ref "SI2") (pin "9") (pinfunction "9_9") (pintype "passive"))
    )
    (net (code "117") (name "Net-(R19-Pad2)") (class "Default")
      (node (ref "R19") (pin "2") (pinfunction "2_2") (pintype "passive"))
      (node (ref "SI2") (pin "7") (pinfunction "7_7") (pintype "passive"))
    )
    (net (code "118") (name "Net-(R20-Pad2)") (class "Default")
      (node (ref "R20") (pin "2") (pinfunction "2_2") (pintype "passive"))
      (node (ref "SI2") (pin "5") (pinfunction "5_5") (pintype "passive"))
    )
    (net (code "119") (name "Net-(R21-Pad2)") (class "Default")
      (node (ref "R21") (pin "2") (pinfunction "2_2") (pintype "passive"))
      (node (ref "SI2") (pin "3") (pinfunction "3_3") (pintype "passive"))
    )
    (net (code "120") (name "Net-(R22-Pad2)") (class "Default")
      (node (ref "R22") (pin "2") (pinfunction "2_2") (pintype "passive"))
      (node (ref "SI2") (pin "1") (pinfunction "1_1") (pintype "passive"))
    )
    (net (code "121") (name "OCX0") (class "Default")
      (node (ref "IC1") (pin "25") (pinfunction "(OC1B/PCINT6)PB6_25") (pintype "bidirectional"))
      (node (ref "IC5") (pin "3") (pinfunction "I1_3") (pintype "input"))
    )
    (net (code "122") (name "OCX1") (class "Default")
      (node (ref "IC1") (pin "26") (pinfunction "(OC0A/OC1C/PCINT7)PB7_26") (pintype "bidirectional"))
      (node (ref "IC5") (pin "6") (pinfunction "I2_6") (pintype "input"))
    )
    (net (code "123") (name "OCX2") (class "Default")
      (node (ref "IC1") (pin "6") (pinfunction "(OC3B/INT4)PE4_6") (pintype "bidirectional"))
      (node (ref "IC5") (pin "11") (pinfunction "I3_11") (pintype "input"))
    )
    (net (code "124") (name "OCX3") (class "Default")
      (node (ref "IC1") (pin "7") (pinfunction "(OC3C/INT5)PE5_7") (pintype "bidirectional"))
      (node (ref "IC5") (pin "14") (pinfunction "I4_14") (pintype "input"))
    )
    (net (code "125") (name "OCX4") (class "Default")
      (node (ref "IC1") (pin "16") (pinfunction "PH4(OC4B)_16") (pintype "bidirectional"))
      (node (ref "IC7") (pin "4") (pinfunction "I4_4") (pintype "input"))
    )
    (net (code "126") (name "OCX5") (class "Default")
      (node (ref "IC1") (pin "17") (pinfunction "PH5(OC4C)_17") (pintype "bidirectional"))
      (node (ref "IC7") (pin "3") (pinfunction "I3_3") (pintype "input"))
    )
    (net (code "127") (name "OCX6") (class "Default")
      (node (ref "IC1") (pin "39") (pinfunction "PL4(OC5B)_39") (pintype "bidirectional"))
      (node (ref "IC7") (pin "2") (pinfunction "I2_2") (pintype "input"))
    )
    (net (code "128") (name "OCX7") (class "Default")
      (node (ref "IC1") (pin "40") (pinfunction "PL5(OC5C)_40") (pintype "bidirectional"))
      (node (ref "IC7") (pin "1") (pinfunction "I1_1") (pintype "input"))
    )
    (net (code "129") (name "PA0") (class "Default")
      (node (ref "IC1") (pin "78") (pinfunction "(AD0)PA0_78") (pintype "bidirectional"))
      (node (ref "IC6") (pin "3") (pinfunction "I1_3") (pintype "input"))
    )
    (net (code "130") (name "PA1") (class "Default")
      (node (ref "IC1") (pin "77") (pinfunction "(AD1)PA1_77") (pintype "bidirectional"))
      (node (ref "IC6") (pin "6") (pinfunction "I2_6") (pintype "input"))
    )
    (net (code "131") (name "PA2") (class "Default")
      (node (ref "IC1") (pin "76") (pinfunction "(AD2)PA2_76") (pintype "bidirectional"))
      (node (ref "IC6") (pin "11") (pinfunction "I3_11") (pintype "input"))
    )
    (net (code "132") (name "PA3") (class "Default")
      (node (ref "IC1") (pin "75") (pinfunction "(AD3)PA3_75") (pintype "bidirectional"))
      (node (ref "IC6") (pin "14") (pinfunction "I4_14") (pintype "input"))
    )
    (net (code "133") (name "PA4") (class "Default")
      (node (ref "IC1") (pin "74") (pinfunction "(AD4)PA4_74") (pintype "bidirectional"))
      (node (ref "IC7") (pin "8") (pinfunction "I8_8") (pintype "input"))
    )
    (net (code "134") (name "PA5") (class "Default")
      (node (ref "IC1") (pin "73") (pinfunction "(AD5)PA5_73") (pintype "bidirectional"))
      (node (ref "IC7") (pin "7") (pinfunction "I7_7") (pintype "input"))
    )
    (net (code "135") (name "PA6") (class "Default")
      (node (ref "IC1") (pin "72") (pinfunction "(AD6)PA6_72") (pintype "bidirectional"))
      (node (ref "IC7") (pin "6") (pinfunction "I6_6") (pintype "input"))
    )
    (net (code "136") (name "PA7") (class "Default")
      (node (ref "IC1") (pin "71") (pinfunction "(AD7)PA7_71") (pintype "bidirectional"))
      (node (ref "IC7") (pin "5") (pinfunction "I5_5") (pintype "input"))
    )
    (net (code "137") (name "PC0") (class "Default")
      (node (ref "IC1") (pin "53") (pinfunction "(A8)PC0_53") (pintype "bidirectional"))
      (node (ref "IC8") (pin "8") (pinfunction "I8_8") (pintype "input"))
    )
    (net (code "138") (name "PC1") (class "Default")
      (node (ref "IC1") (pin "54") (pinfunction "(A9)PC1_54") (pintype "bidirectional"))
      (node (ref "IC8") (pin "7") (pinfunction "I7_7") (pintype "input"))
    )
    (net (code "139") (name "PC2") (class "Default")
      (node (ref "IC1") (pin "55") (pinfunction "(A10)PC2_55") (pintype "bidirectional"))
      (node (ref "IC8") (pin "6") (pinfunction "I6_6") (pintype "input"))
    )
    (net (code "140") (name "PC3") (class "Default")
      (node (ref "IC1") (pin "56") (pinfunction "(A11)PC3_56") (pintype "bidirectional"))
      (node (ref "IC8") (pin "5") (pinfunction "I5_5") (pintype "input"))
    )
    (net (code "141") (name "PC4") (class "Default")
      (node (ref "IC1") (pin "57") (pinfunction "(A12)PC4_57") (pintype "bidirectional"))
      (node (ref "IC8") (pin "4") (pinfunction "I4_4") (pintype "input"))
    )
    (net (code "142") (name "PC5") (class "Default")
      (node (ref "IC1") (pin "58") (pinfunction "(A13)PC5_58") (pintype "bidirectional"))
      (node (ref "IC8") (pin "3") (pinfunction "I3_3") (pintype "input"))
    )
    (net (code "143") (name "PC6") (class "Default")
      (node (ref "IC1") (pin "59") (pinfunction "(A14)PC6_59") (pintype "bidirectional"))
      (node (ref "IC8") (pin "2") (pinfunction "I2_2") (pintype "input"))
    )
    (net (code "144") (name "PC7") (class "Default")
      (node (ref "IC1") (pin "60") (pinfunction "(A15)PC7_60") (pintype "bidirectional"))
      (node (ref "IC8") (pin "1") (pinfunction "I1_1") (pintype "input"))
    )
    (net (code "145") (name "PD0") (class "Default")
      (node (ref "IC1") (pin "43") (pinfunction "(SCL/INT0)PD0_43") (pintype "bidirectional"))
      (node (ref "OK3") (pin "7") (pinfunction "VOUT1_7") (pintype "output"))
    )
    (net (code "146") (name "PD1") (class "Default")
      (node (ref "IC1") (pin "44") (pinfunction "(SDA/INT1)PD1_44") (pintype "bidirectional"))
      (node (ref "OK3") (pin "6") (pinfunction "VOUT2_6") (pintype "output"))
    )
    (net (code "147") (name "PD2") (class "Default")
      (node (ref "IC1") (pin "45") (pinfunction "(RXD1/INT2)PD2_45") (pintype "bidirectional"))
      (node (ref "OK4") (pin "7") (pinfunction "VOUT1_7") (pintype "output"))
    )
    (net (code "148") (name "PD3") (class "Default")
      (node (ref "IC1") (pin "46") (pinfunction "(TXD1/INT3)PD3_46") (pintype "bidirectional"))
      (node (ref "OK4") (pin "6") (pinfunction "VOUT2_6") (pintype "output"))
    )
    (net (code "149") (name "PD4") (class "Default")
      (node (ref "IC1") (pin "47") (pinfunction "(ICP1)PD4_47") (pintype "bidirectional"))
      (node (ref "OK5") (pin "7") (pinfunction "VOUT1_7") (pintype "output"))
    )
    (net (code "150") (name "PD5") (class "Default")
      (node (ref "IC1") (pin "48") (pinfunction "(XCK1)PD5_48") (pintype "bidirectional"))
      (node (ref "OK5") (pin "6") (pinfunction "VOUT2_6") (pintype "output"))
    )
    (net (code "151") (name "PD6") (class "Default")
      (node (ref "IC1") (pin "49") (pinfunction "(T1)PD6_49") (pintype "bidirectional"))
      (node (ref "OK6") (pin "7") (pinfunction "VOUT1_7") (pintype "output"))
    )
    (net (code "152") (name "PD7") (class "Default")
      (node (ref "IC1") (pin "50") (pinfunction "(T0)PD7_50") (pintype "bidirectional"))
      (node (ref "OK6") (pin "6") (pinfunction "VOUT2_6") (pintype "output"))
    )
    (net (code "153") (name "PE1") (class "Default")
      (node (ref "IC1") (pin "3") (pinfunction "(TXD0)PE1_3") (pintype "bidirectional"))
      (node (ref "IC3") (pin "5") (pinfunction "SDI_5") (pintype "input"))
    )
    (net (code "154") (name "PE2") (class "Default")
      (node (ref "IC1") (pin "4") (pinfunction "(XCK0/AIN0)PE2_4") (pintype "bidirectional"))
      (node (ref "IC3") (pin "4") (pinfunction "SCK_4") (pintype "input"))
    )
    (net (code "155") (name "PE3") (class "Default")
      (node (ref "IC1") (pin "5") (pinfunction "(OC3A/AIN1)PE3_5") (pintype "bidirectional"))
      (node (ref "IC3") (pin "3") (pinfunction "~{CS}_3") (pintype "input"))
    )
    (net (code "156") (name "PE6") (class "Default")
      (node (ref "IC1") (pin "8") (pinfunction "(T3/INT6)PE6_8") (pintype "bidirectional"))
      (node (ref "IC3") (pin "9") (pinfunction "~{SHDN}_9") (pintype "input"))
    )
    (net (code "157") (name "PE7") (class "Default")
      (node (ref "IC1") (pin "9") (pinfunction "(CLKO/ICP3/INT7)PE7_9") (pintype "bidirectional"))
      (node (ref "IC3") (pin "8") (pinfunction "~{LDAC}_8") (pintype "input"))
    )
    (net (code "158") (name "PH0") (class "Default")
      (node (ref "IC1") (pin "12") (pinfunction "PH0(RXD2)_12") (pintype "bidirectional"))
      (node (ref "IC2") (pin "1") (pinfunction "TXD_1") (pintype "input"))
    )
    (net (code "159") (name "PH1") (class "Default")
      (node (ref "IC1") (pin "13") (pinfunction "PH1(TXD2)_13") (pintype "bidirectional"))
      (node (ref "IC2") (pin "5") (pinfunction "RXD_5") (pintype "input"))
    )
    (net (code "160") (name "PH2") (class "Default")
      (node (ref "IC1") (pin "14") (pinfunction "PH2(XCK2)_14") (pintype "bidirectional"))
      (node (ref "IC2") (pin "3") (pinfunction "~{RTS}_3") (pintype "input"))
    )
    (net (code "161") (name "PH3") (class "Default")
      (node (ref "IC1") (pin "15") (pinfunction "PH3(OC4A)_15") (pintype "bidirectional"))
      (node (ref "IC2") (pin "11") (pinfunction "~{CTS}_11") (pintype "input"))
    )
    (net (code "162") (name "PJ0") (class "Default")
      (node (ref "IC1") (pin "63") (pinfunction "PJ0(RXD3/PCINT9)_63") (pintype "bidirectional"))
      (node (ref "OK1") (pin "15") (pinfunction "COL_15") (pintype "passive"))
    )
    (net (code "163") (name "PJ1") (class "Default")
      (node (ref "IC1") (pin "64") (pinfunction "PJ1(TXD3/PCINT10)_64") (pintype "bidirectional"))
      (node (ref "OK1") (pin "14") (pinfunction "COL_14") (pintype "passive"))
    )
    (net (code "164") (name "PJ2") (class "Default")
      (node (ref "IC1") (pin "65") (pinfunction "PJ2(XCK3/PCINT11)_65") (pintype "bidirectional"))
      (node (ref "OK1") (pin "11") (pinfunction "COL_11") (pintype "passive"))
    )
    (net (code "165") (name "PJ3") (class "Default")
      (node (ref "IC1") (pin "66") (pinfunction "PJ3(PCINT12)_66") (pintype "bidirectional"))
      (node (ref "OK1") (pin "10") (pinfunction "COL_10") (pintype "passive"))
    )
    (net (code "166") (name "PJ4") (class "Default")
      (node (ref "IC1") (pin "67") (pinfunction "PJ4(PCINT13)_67") (pintype "bidirectional"))
      (node (ref "OK2") (pin "15") (pinfunction "COL_15") (pintype "passive"))
    )
    (net (code "167") (name "PJ5") (class "Default")
      (node (ref "IC1") (pin "68") (pinfunction "PJ5(PCINT14)_68") (pintype "bidirectional"))
      (node (ref "OK2") (pin "14") (pinfunction "COL_14") (pintype "passive"))
    )
    (net (code "168") (name "PJ6") (class "Default")
      (node (ref "IC1") (pin "69") (pinfunction "PJ6(PCINT15)_69") (pintype "bidirectional"))
      (node (ref "OK2") (pin "11") (pinfunction "COL_11") (pintype "passive"))
    )
    (net (code "169") (name "PJ7") (class "Default")
      (node (ref "IC1") (pin "79") (pinfunction "PJ7_79") (pintype "bidirectional"))
      (node (ref "OK2") (pin "10") (pinfunction "COL_10") (pintype "passive"))
    )
    (net (code "170") (name "PL7") (class "Default")
      (node (ref "IC1") (pin "42") (pinfunction "PL7_42") (pintype "bidirectional"))
      (node (ref "Q2") (pin "1") (pinfunction "GATE_1") (pintype "passive"))
    )
    (net (code "171") (name "PWREN") (class "Default")
      (node (ref "IC1") (pin "24") (pinfunction "(OC1A/PCINT5)PB5_24") (pintype "bidirectional"))
      (node (ref "IC2") (pin "14") (pinfunction "CBUS3_14") (pintype "input"))
      (node (ref "R4") (pin "1") (pinfunction "1_1") (pintype "passive"))
    )
    (net (code "172") (name "RESET") (class "Default")
      (node (ref "IC1") (pin "23") (pinfunction "(OC2A/PCINT4)PB4_23") (pintype "bidirectional"))
      (node (ref "IC2") (pin "19") (pinfunction "~{RESET}_19") (pintype "input"))
      (node (ref "R14") (pin "2") (pinfunction "2_2") (pintype "passive"))
    )
    (net (code "173") (name "RXLED") (class "Default")
      (node (ref "IC2") (pin "22") (pinfunction "CBUS1_22") (pintype "input"))
      (node (ref "RXLED") (pin "K") (pinfunction "C_K") (pintype "passive"))
    )
    (net (code "174") (name "TXLED") (class "Default")
      (node (ref "IC2") (pin "23") (pinfunction "CBUS0_23") (pintype "input"))
      (node (ref "TXLED") (pin "K") (pinfunction "C_K") (pintype "passive"))
    )
    (net (code "175") (name "VCC") (class "Default")
      (node (ref "AI1") (pin "10") (pinfunction "10_10") (pintype "passive"))
      (node (ref "AI2") (pin "10") (pinfunction "10_10") (pintype "passive"))
      (node (ref "C10") (pin "1") (pinfunction "1_1") (pintype "passive"))
      (node (ref "C11") (pin "1") (pinfunction "1_1") (pintype "passive"))
      (node (ref "C12") (pin "1") (pinfunction "1_1") (pintype "passive"))
      (node (ref "C20") (pin "1") (pinfunction "1_1") (pintype "passive"))
      (node (ref "C21") (pin "1") (pinfunction "1_1") (pintype "passive"))
      (node (ref "C22") (pin "1") (pinfunction "1_1") (pintype "passive"))
      (node (ref "C23") (pin "1") (pinfunction "1_1") (pintype "passive"))
      (node (ref "C24") (pin "1") (pinfunction "1_1") (pintype "passive"))
      (node (ref "C25") (pin "1") (pinfunction "1_1") (pintype "passive"))
      (node (ref "C4") (pin "1") (pinfunction "1_1") (pintype "passive"))
      (node (ref "C5") (pin "1") (pinfunction "1_1") (pintype "passive"))
      (node (ref "C6") (pin "1") (pinfunction "1_1") (pintype "passive"))
      (node (ref "C9") (pin "1") (pinfunction "1_1") (pintype "passive"))
      (node (ref "IC1") (pin "10") (pinfunction "VCC_10") (pintype "power_in"))
      (node (ref "IC1") (pin "31") (pinfunction "VCC1_31") (pintype "power_in"))
      (node (ref "IC1") (pin "61") (pinfunction "VCC2_61") (pintype "power_in"))
      (node (ref "IC1") (pin "80") (pinfunction "VCC3_80") (pintype "power_in"))
      (node (ref "IC2") (pin "20") (pinfunction "VCC_20") (pintype "input"))
      (node (ref "IC2") (pin "4") (pinfunction "VCCIO_4") (pintype "input"))
      (node (ref "IC3") (pin "1") (pinfunction "VDD_1") (pintype "power_in"))
      (node (ref "L1") (pin "2") (pinfunction "2_2") (pintype "passive"))
      (node (ref "L2") (pin "2") (pinfunction "2_2") (pintype "passive"))
      (node (ref "Q2") (pin "3") (pinfunction "DRAIN_3") (pintype "passive"))
      (node (ref "R1") (pin "1") (pinfunction "1_1") (pintype "passive"))
      (node (ref "R13") (pin "2") (pinfunction "2_2") (pintype "passive"))
      (node (ref "R14") (pin "1") (pinfunction "1_1") (pintype "passive"))
      (node (ref "R2") (pin "1") (pinfunction "1_1") (pintype "passive"))
      (node (ref "R3") (pin "2") (pinfunction "2_2") (pintype "passive"))
      (node (ref "R4") (pin "2") (pinfunction "2_2") (pintype "passive"))
    )
    (net (code "176") (name "VCC{slash}2") (class "Default")
      (node (ref "CON1") (pin "VCC") (pinfunction "+VCC_VCC") (pintype "power_in"))
      (node (ref "LO3") (pin "1") (pinfunction "1_1") (pintype "passive"))
      (node (ref "SO4") (pin "1") (pinfunction "1_1") (pintype "passive"))
      (node (ref "SO5") (pin "1") (pinfunction "1_1") (pintype "passive"))
    )
    (net (code "177") (name "VREF") (class "Default")
      (node (ref "AI1") (pin "9") (pinfunction "9_9") (pintype "passive"))
      (node (ref "AI2") (pin "9") (pinfunction "9_9") (pintype "passive"))
      (node (ref "C26") (pin "1") (pinfunction "1_1") (pintype "passive"))
      (node (ref "C27") (pin "1") (pinfunction "1_1") (pintype "passive"))
      (node (ref "C7") (pin "2") (pinfunction "2_2") (pintype "passive"))
      (node (ref "IC1") (pin "98") (pinfunction "AREF_98") (pintype "bidirectional"))
      (node (ref "IC3") (pin "11") (pinfunction "VREFB_11") (pintype "input"))
      (node (ref "IC3") (pin "13") (pinfunction "VREFA_13") (pintype "input"))
      (node (ref "IC4") (pin "2") (pinfunction "CAT_2") (pintype "passive"))
      (node (ref "IL1") (pin "4") (pinfunction "4_4") (pintype "passive"))
      (node (ref "R13") (pin "1") (pinfunction "1_1") (pintype "passive"))
    )
    (net (code "178") (name "unconnected-(F1-Pad1B)") (class "Default")
      (node (ref "F1") (pin "1B") (pinfunction "1B_1B") (pintype "passive"))
    )
    (net (code "179") (name "unconnected-(F1-Pad2B)") (class "Default")
      (node (ref "F1") (pin "2B") (pinfunction "2B_2B") (pintype "passive"))
    )
    (net (code "180") (name "unconnected-(IC1-(ALE)PG2-Pad70)") (class "Default")
      (node (ref "IC1") (pin "70") (pinfunction "(ALE)PG2_70") (pintype "bidirectional"))
    )
    (net (code "181") (name "unconnected-(IC1-(OC0B)PG5-Pad1)") (class "Default")
      (node (ref "IC1") (pin "1") (pinfunction "(OC0B)PG5_1") (pintype "bidirectional"))
    )
    (net (code "182") (name "unconnected-(IC1-(RD)PG1-Pad52)") (class "Default")
      (node (ref "IC1") (pin "52") (pinfunction "(RD)PG1_52") (pintype "bidirectional"))
    )
    (net (code "183") (name "unconnected-(IC1-(RXD0{slash}PCIN8)PE0-Pad2)") (class "Default")
      (node (ref "IC1") (pin "2") (pinfunction "(RXD0/PCIN8)PE0_2") (pintype "bidirectional"))
    )
    (net (code "184") (name "unconnected-(IC1-(TOSC1)PG4-Pad29)") (class "Default")
      (node (ref "IC1") (pin "29") (pinfunction "(TOSC1)PG4_29") (pintype "bidirectional"))
    )
    (net (code "185") (name "unconnected-(IC1-(TOSC2)PG3-Pad28)") (class "Default")
      (node (ref "IC1") (pin "28") (pinfunction "(TOSC2)PG3_28") (pintype "bidirectional"))
    )
    (net (code "186") (name "unconnected-(IC1-(WR)PG0-Pad51)") (class "Default")
      (node (ref "IC1") (pin "51") (pinfunction "(WR)PG0_51") (pintype "bidirectional"))
    )
    (net (code "187") (name "unconnected-(IC1-PH6(OC2B)-Pad18)") (class "Default")
      (node (ref "IC1") (pin "18") (pinfunction "PH6(OC2B)_18") (pintype "bidirectional"))
    )
    (net (code "188") (name "unconnected-(IC1-PH7(T4)-Pad27)") (class "Default")
      (node (ref "IC1") (pin "27") (pinfunction "PH7(T4)_27") (pintype "bidirectional"))
    )
    (net (code "189") (name "unconnected-(IC1-PL0(ICP4)-Pad35)") (class "Default")
      (node (ref "IC1") (pin "35") (pinfunction "PL0(ICP4)_35") (pintype "bidirectional"))
    )
    (net (code "190") (name "unconnected-(IC1-PL1(ICP5)-Pad36)") (class "Default")
      (node (ref "IC1") (pin "36") (pinfunction "PL1(ICP5)_36") (pintype "bidirectional"))
    )
    (net (code "191") (name "unconnected-(IC1-PL2(T5)-Pad37)") (class "Default")
      (node (ref "IC1") (pin "37") (pinfunction "PL2(T5)_37") (pintype "bidirectional"))
    )
    (net (code "192") (name "unconnected-(IC1-PL3(OC5A)-Pad38)") (class "Default")
      (node (ref "IC1") (pin "38") (pinfunction "PL3(OC5A)_38") (pintype "bidirectional"))
    )
    (net (code "193") (name "unconnected-(IC1-PL6-Pad41)") (class "Default")
      (node (ref "IC1") (pin "41") (pinfunction "PL6_41") (pintype "bidirectional"))
    )
    (net (code "194") (name "unconnected-(IC2-CBUS2-Pad13)") (class "Default")
      (node (ref "IC2") (pin "13") (pinfunction "CBUS2_13") (pintype "input"))
    )
    (net (code "195") (name "unconnected-(IC2-OSCI-Pad27)") (class "Default")
      (node (ref "IC2") (pin "27") (pinfunction "OSCI_27") (pintype "input"))
    )
    (net (code "196") (name "unconnected-(IC2-OSCO-Pad28)") (class "Default")
      (node (ref "IC2") (pin "28") (pinfunction "OSCO_28") (pintype "input"))
    )
    (net (code "197") (name "~{SLEEP}") (class "Default")
      (node (ref "IC1") (pin "19") (pinfunction "(SS/PCINT0)PB0_19") (pintype "bidirectional"))
      (node (ref "IC2") (pin "12") (pinfunction "CBUS4_12") (pintype "input"))
    )
  )
)
